# adu.net
KiCad netlist of a schematic drawn in Altium Designer
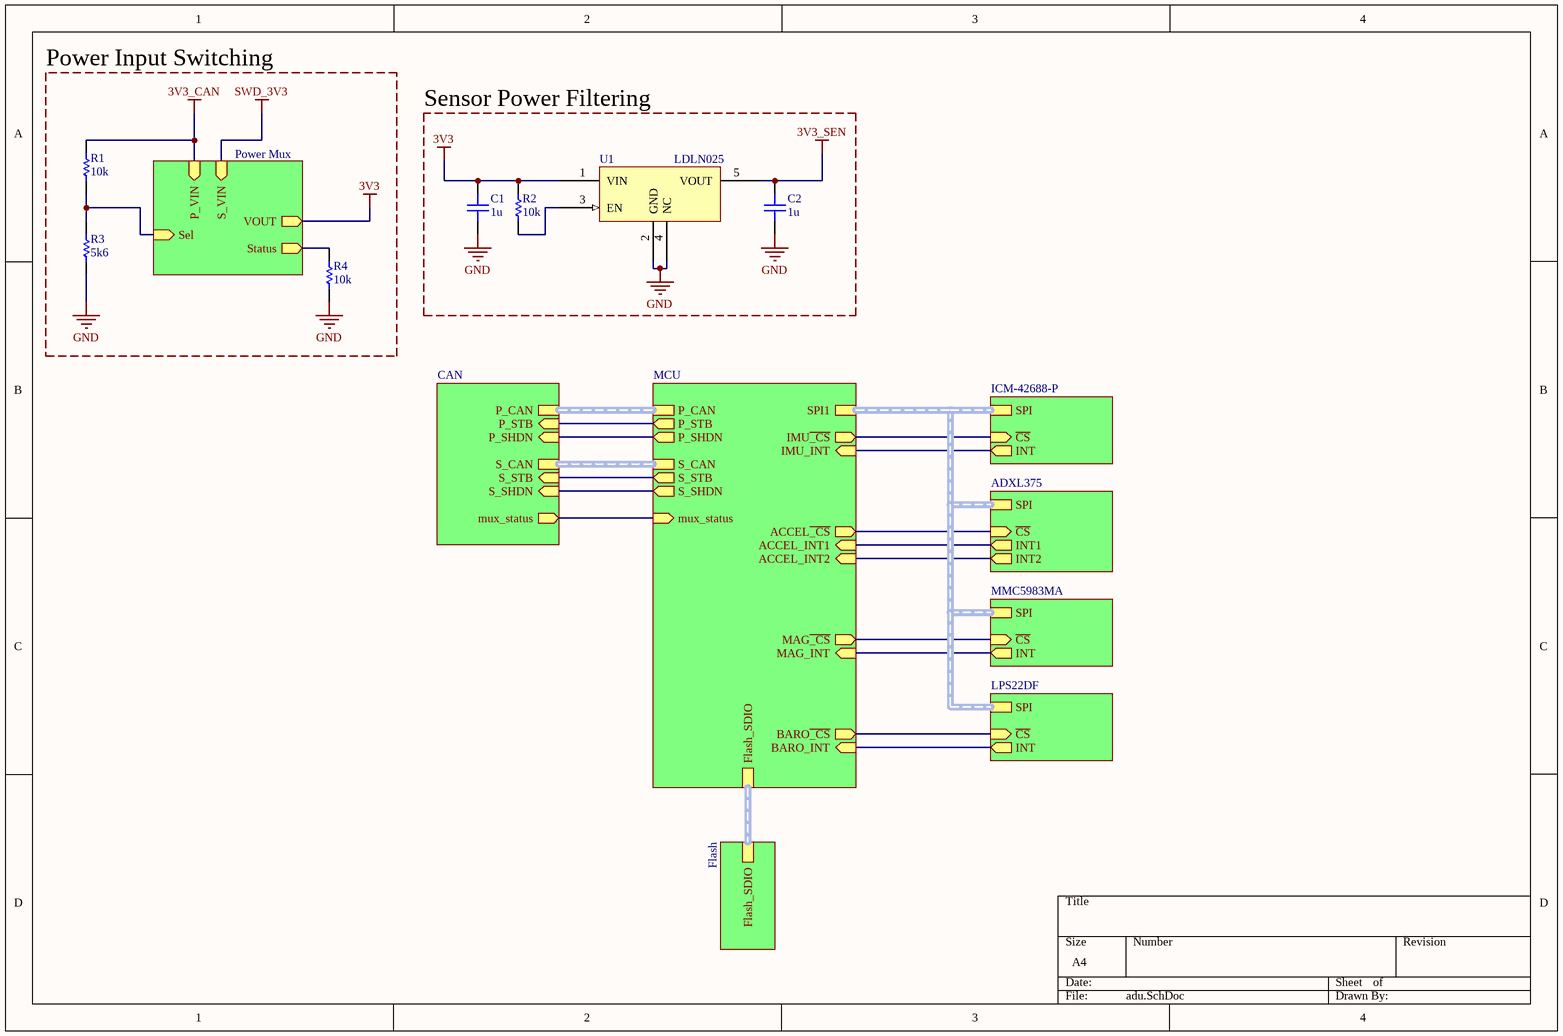
[diagram p0: adu.SchDoc]

(export (version "E")
  (design (tool "Eeschema 10.0.6"))
  (components
    (comp (ref "C1")
      (value "1u")
      (footprint "CAP-0603-NP")
      (description "Capacitor")
      (libsource (lib "drfc_schlib") (part "Capacitor"))
    )
    (comp (ref "C2")
      (value "1u")
      (footprint "CAP-0603-NP")
      (description "Capacitor")
      (libsource (lib "drfc_schlib") (part "Capacitor"))
    )
    (comp (ref "R1")
      (value "10k")
      (footprint "RES-0603")
      (description "Resistor")
      (libsource (lib "drfc_schlib") (part "Resistor"))
    )
    (comp (ref "R2")
      (value "10k")
      (footprint "RES-0603")
      (description "Resistor")
      (libsource (lib "drfc_schlib") (part "Resistor"))
    )
    (comp (ref "R3")
      (value "5k6")
      (footprint "RES-0603")
      (description "Resistor")
      (libsource (lib "drfc_schlib") (part "Resistor"))
    )
    (comp (ref "R4")
      (value "10k")
      (footprint "RES-0603")
      (description "Resistor")
      (libsource (lib "drfc_schlib") (part "Resistor"))
    )
    (comp (ref "U1")
      (value "LDLN025")
      (footprint "ST SOT23-5L")
      (description "250 mA ultra low noise LDO")
      (libsource (lib "drfc_schlib") (part "LDLN025"))
    )
  )
  (nets
    (net (code "18") (name "/Sel") (class "Default")
      (node (ref "R1") (pin "1") (pinfunction "1_1") (pintype "passive"))
      (node (ref "R3") (pin "2") (pinfunction "2_2") (pintype "passive"))
    )
    (net (code "19") (name "/Status") (class "Default")
      (node (ref "R4") (pin "2") (pinfunction "2_2") (pintype "passive"))
    )
    (net (code "21") (name "3V3") (class "Default")
      (node (ref "C1") (pin "2") (pinfunction "2_2") (pintype "passive"))
      (node (ref "R2") (pin "2") (pinfunction "2_2") (pintype "passive"))
      (node (ref "U1") (pin "1") (pinfunction "VIN_1") (pintype "power_in"))
    )
    (net (code "22") (name "3V3_CAN") (class "Default")
      (node (ref "R1") (pin "2") (pinfunction "2_2") (pintype "passive"))
    )
    (net (code "23") (name "3V3_SEN") (class "Default")
      (node (ref "C2") (pin "2") (pinfunction "2_2") (pintype "passive"))
      (node (ref "U1") (pin "5") (pinfunction "VOUT_5") (pintype "power_in"))
    )
    (net (code "24") (name "GND") (class "Default")
      (node (ref "C1") (pin "1") (pinfunction "1_1") (pintype "passive"))
      (node (ref "C2") (pin "1") (pinfunction "1_1") (pintype "passive"))
      (node (ref "R3") (pin "1") (pinfunction "1_1") (pintype "passive"))
      (node (ref "R4") (pin "1") (pinfunction "1_1") (pintype "passive"))
      (node (ref "U1") (pin "2") (pinfunction "GND_2") (pintype "power_in"))
      (node (ref "U1") (pin "4") (pinfunction "NC_4") (pintype "power_in"))
    )
    (net (code "25") (name "Net-(U1-EN)") (class "Default")
      (node (ref "R2") (pin "1") (pinfunction "1_1") (pintype "passive"))
      (node (ref "U1") (pin "3") (pinfunction "EN_3") (pintype "input"))
    )
  )
)
